# light_controller.net
KiCad netlist of a schematic drawn in EAGLE
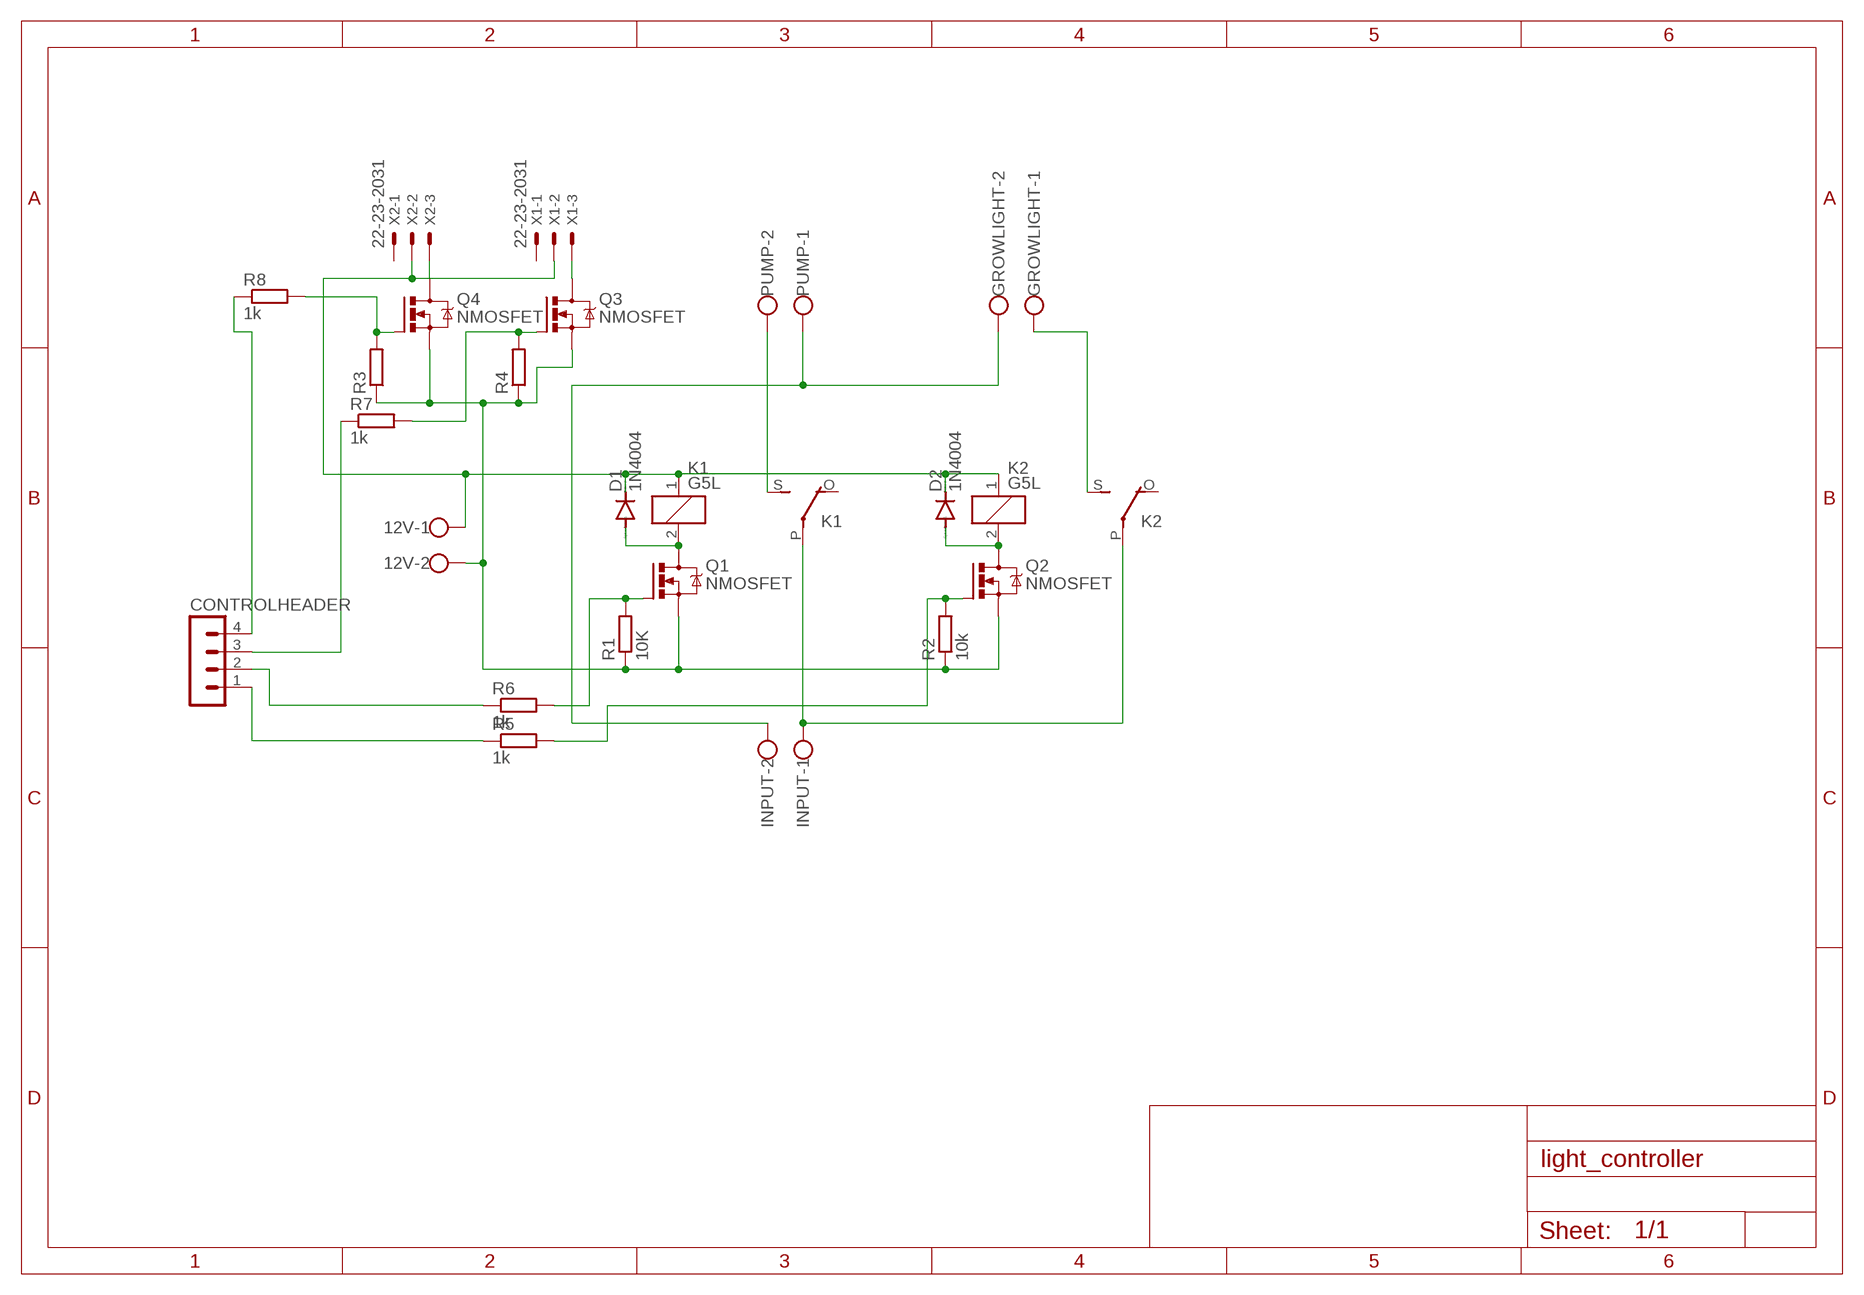
[diagram p0: schematic, sheet 1]

(export (version "E")
  (design (tool "Eeschema 10.0.6"))
  (components
    (comp (ref "12V")
      (value "W237-102")
      (footprint "eagle-import:W237-102")
      (fields (field (name "MPN") "237-102"))
      (libsource (lib "eagle-import") (part "W237-102"))
    )
    (comp (ref "CONTROLHEADER")
      (value "MA04-1")
      (footprint "eagle-import:MA04-1")
      (libsource (lib "eagle-import") (part "MA04-1"))
    )
    (comp (ref "D1")
      (value "1N4004")
      (footprint "eagle-import:DO41-10")
      (libsource (lib "eagle-import") (part "1N4004"))
    )
    (comp (ref "D2")
      (value "1N4004")
      (footprint "eagle-import:DO41-10")
      (libsource (lib "eagle-import") (part "1N4004"))
    )
    (comp (ref "GROWLIGHT")
      (value "W237-102")
      (footprint "eagle-import:W237-102")
      (fields (field (name "MPN") "237-102"))
      (libsource (lib "eagle-import") (part "W237-102"))
    )
    (comp (ref "INPUT")
      (value "W237-102")
      (footprint "eagle-import:W237-102")
      (fields (field (name "MPN") "237-102"))
      (libsource (lib "eagle-import") (part "W237-102"))
    )
    (comp (ref "K1")
      (value "G5L")
      (footprint "eagle-import:G5LE")
      (libsource (lib "eagle-import") (part "G5L"))
    )
    (comp (ref "K2")
      (value "G5L")
      (footprint "eagle-import:G5LE")
      (libsource (lib "eagle-import") (part "G5L"))
    )
    (comp (ref "PUMP")
      (value "W237-102")
      (footprint "eagle-import:W237-102")
      (fields (field (name "MPN") "237-102"))
      (libsource (lib "eagle-import") (part "W237-102"))
    )
    (comp (ref "Q1")
      (value "NMOSFET")
      (footprint "eagle-import:TO220BV")
      (libsource (lib "eagle-import") (part "NMOSFETTO220_"))
    )
    (comp (ref "Q2")
      (value "NMOSFET")
      (footprint "eagle-import:TO220BV")
      (libsource (lib "eagle-import") (part "NMOSFETTO220_"))
    )
    (comp (ref "Q3")
      (value "NMOSFET")
      (footprint "eagle-import:TO220BV")
      (libsource (lib "eagle-import") (part "NMOSFETTO220_"))
    )
    (comp (ref "Q4")
      (value "NMOSFET")
      (footprint "eagle-import:TO220BV")
      (libsource (lib "eagle-import") (part "NMOSFETTO220_"))
    )
    (comp (ref "R1")
      (value "10K")
      (footprint "eagle-import:0204_7")
      (libsource (lib "eagle-import") (part "R-EU_0204/7"))
    )
    (comp (ref "R2")
      (value "10k")
      (footprint "eagle-import:0204_7")
      (libsource (lib "eagle-import") (part "R-EU_0204/7"))
    )
    (comp (ref "R3")
      (value "R-EU_0204/7")
      (footprint "eagle-import:0204_7")
      (libsource (lib "eagle-import") (part "R-EU_0204/7"))
    )
    (comp (ref "R4")
      (value "R-EU_0204/7")
      (footprint "eagle-import:0204_7")
      (libsource (lib "eagle-import") (part "R-EU_0204/7"))
    )
    (comp (ref "R5")
      (value "1k")
      (footprint "eagle-import:0204_7")
      (libsource (lib "eagle-import") (part "R-EU_0204/7"))
    )
    (comp (ref "R6")
      (value "1k")
      (footprint "eagle-import:0204_7")
      (libsource (lib "eagle-import") (part "R-EU_0204/7"))
    )
    (comp (ref "R7")
      (value "1k")
      (footprint "eagle-import:0204_7")
      (libsource (lib "eagle-import") (part "R-EU_0204/7"))
    )
    (comp (ref "R8")
      (value "1k")
      (footprint "eagle-import:0204_7")
      (libsource (lib "eagle-import") (part "R-EU_0204/7"))
    )
    (comp (ref "X1")
      (value "22-23-2031")
      (footprint "eagle-import:22-23-2031")
      (fields (field (name "MF") "MOLEX"))
      (libsource (lib "eagle-import") (part "22-23-2031"))
    )
    (comp (ref "X2")
      (value "22-23-2031")
      (footprint "eagle-import:22-23-2031")
      (fields (field (name "MF") "MOLEX"))
      (libsource (lib "eagle-import") (part "22-23-2031"))
    )
  )
  (nets
    (net (code "1") (name "Net-(12VA-KL)") (class "Default")
      (node (ref "12V") (pin "1") (pinfunction "KL_1") (pintype "passive"))
      (node (ref "D1") (pin "C") (pinfunction "C_C") (pintype "passive"))
      (node (ref "D2") (pin "C") (pinfunction "C_C") (pintype "passive"))
      (node (ref "K1") (pin "1") (pinfunction "1_1") (pintype "passive"))
      (node (ref "K2") (pin "1") (pinfunction "1_1") (pintype "passive"))
      (node (ref "X1") (pin "2") (pinfunction "S_2") (pintype "passive"))
      (node (ref "X2") (pin "2") (pinfunction "S_2") (pintype "passive"))
    )
    (net (code "2") (name "Net-(12VB-KL)") (class "Default")
      (node (ref "12V") (pin "2") (pinfunction "KL_2") (pintype "passive"))
      (node (ref "Q1") (pin "S") (pinfunction "S_S") (pintype "passive"))
      (node (ref "Q2") (pin "S") (pinfunction "S_S") (pintype "passive"))
      (node (ref "Q3") (pin "S") (pinfunction "S_S") (pintype "passive"))
      (node (ref "Q4") (pin "S") (pinfunction "S_S") (pintype "passive"))
      (node (ref "R1") (pin "1") (pinfunction "1_1") (pintype "passive"))
      (node (ref "R2") (pin "1") (pinfunction "1_1") (pintype "passive"))
      (node (ref "R3") (pin "1") (pinfunction "1_1") (pintype "passive"))
      (node (ref "R4") (pin "1") (pinfunction "1_1") (pintype "passive"))
    )
    (net (code "3") (name "Net-(CONTROLHEADER-Pad1)") (class "Default")
      (node (ref "CONTROLHEADER") (pin "1") (pinfunction "1_1") (pintype "passive"))
      (node (ref "R5") (pin "1") (pinfunction "1_1") (pintype "passive"))
    )
    (net (code "4") (name "Net-(CONTROLHEADER-Pad2)") (class "Default")
      (node (ref "CONTROLHEADER") (pin "2") (pinfunction "2_2") (pintype "passive"))
      (node (ref "R6") (pin "1") (pinfunction "1_1") (pintype "passive"))
    )
    (net (code "5") (name "Net-(CONTROLHEADER-Pad3)") (class "Default")
      (node (ref "CONTROLHEADER") (pin "3") (pinfunction "3_3") (pintype "passive"))
      (node (ref "R7") (pin "1") (pinfunction "1_1") (pintype "passive"))
    )
    (net (code "6") (name "Net-(CONTROLHEADER-Pad4)") (class "Default")
      (node (ref "CONTROLHEADER") (pin "4") (pinfunction "4_4") (pintype "passive"))
      (node (ref "R8") (pin "1") (pinfunction "1_1") (pintype "passive"))
    )
    (net (code "7") (name "Net-(D1-PadA)") (class "Default")
      (node (ref "D1") (pin "A") (pinfunction "A_A") (pintype "passive"))
      (node (ref "K1") (pin "2") (pinfunction "2_2") (pintype "passive"))
      (node (ref "Q1") (pin "D") (pinfunction "D_D") (pintype "passive"))
    )
    (net (code "8") (name "Net-(D2-PadA)") (class "Default")
      (node (ref "D2") (pin "A") (pinfunction "A_A") (pintype "passive"))
      (node (ref "K2") (pin "2") (pinfunction "2_2") (pintype "passive"))
      (node (ref "Q2") (pin "D") (pinfunction "D_D") (pintype "passive"))
    )
    (net (code "9") (name "Net-(GROWLIGHTA-KL)") (class "Default")
      (node (ref "GROWLIGHT") (pin "1") (pinfunction "KL_1") (pintype "passive"))
      (node (ref "K2") (pin "S") (pinfunction "S_S") (pintype "passive"))
    )
    (net (code "10") (name "Net-(GROWLIGHTB-KL)") (class "Default")
      (node (ref "GROWLIGHT") (pin "2") (pinfunction "KL_2") (pintype "passive"))
      (node (ref "INPUT") (pin "2") (pinfunction "KL_2") (pintype "passive"))
      (node (ref "PUMP") (pin "1") (pinfunction "KL_1") (pintype "passive"))
    )
    (net (code "11") (name "Net-(INPUTA-KL)") (class "Default")
      (node (ref "INPUT") (pin "1") (pinfunction "KL_1") (pintype "passive"))
      (node (ref "K1") (pin "P") (pinfunction "P_P") (pintype "passive"))
      (node (ref "K2") (pin "P") (pinfunction "P_P") (pintype "passive"))
    )
    (net (code "12") (name "Net-(PUMPB-KL)") (class "Default")
      (node (ref "K1") (pin "S") (pinfunction "S_S") (pintype "passive"))
      (node (ref "PUMP") (pin "2") (pinfunction "KL_2") (pintype "passive"))
    )
    (net (code "13") (name "Net-(Q1-PadG)") (class "Default")
      (node (ref "Q1") (pin "G") (pinfunction "G_G") (pintype "passive"))
      (node (ref "R1") (pin "2") (pinfunction "2_2") (pintype "passive"))
      (node (ref "R6") (pin "2") (pinfunction "2_2") (pintype "passive"))
    )
    (net (code "14") (name "Net-(Q2-PadG)") (class "Default")
      (node (ref "Q2") (pin "G") (pinfunction "G_G") (pintype "passive"))
      (node (ref "R2") (pin "2") (pinfunction "2_2") (pintype "passive"))
      (node (ref "R5") (pin "2") (pinfunction "2_2") (pintype "passive"))
    )
    (net (code "15") (name "Net-(Q3-PadG)") (class "Default")
      (node (ref "Q3") (pin "G") (pinfunction "G_G") (pintype "passive"))
      (node (ref "R4") (pin "2") (pinfunction "2_2") (pintype "passive"))
      (node (ref "R7") (pin "2") (pinfunction "2_2") (pintype "passive"))
    )
    (net (code "16") (name "Net-(Q4-PadG)") (class "Default")
      (node (ref "Q4") (pin "G") (pinfunction "G_G") (pintype "passive"))
      (node (ref "R3") (pin "2") (pinfunction "2_2") (pintype "passive"))
      (node (ref "R8") (pin "2") (pinfunction "2_2") (pintype "passive"))
    )
    (net (code "17") (name "Net-(X1C-S)") (class "Default")
      (node (ref "Q3") (pin "D") (pinfunction "D_D") (pintype "passive"))
      (node (ref "X1") (pin "3") (pinfunction "S_3") (pintype "passive"))
    )
    (net (code "18") (name "Net-(X2C-S)") (class "Default")
      (node (ref "Q4") (pin "D") (pinfunction "D_D") (pintype "passive"))
      (node (ref "X2") (pin "3") (pinfunction "S_3") (pintype "passive"))
    )
    (net (code "19") (name "unconnected-(K1-PadO)") (class "Default")
      (node (ref "K1") (pin "O") (pinfunction "O_O") (pintype "passive"))
    )
    (net (code "20") (name "unconnected-(K2-PadO)") (class "Default")
      (node (ref "K2") (pin "O") (pinfunction "O_O") (pintype "passive"))
    )
    (net (code "21") (name "unconnected-(X1A-S-Pad1)") (class "Default")
      (node (ref "X1") (pin "1") (pinfunction "S_1") (pintype "passive"))
    )
    (net (code "22") (name "unconnected-(X2A-S-Pad1)") (class "Default")
      (node (ref "X2") (pin "1") (pinfunction "S_1") (pintype "passive"))
    )
  )
)
